# Schematic.net
KiCad netlist of a schematic drawn in Altium Designer
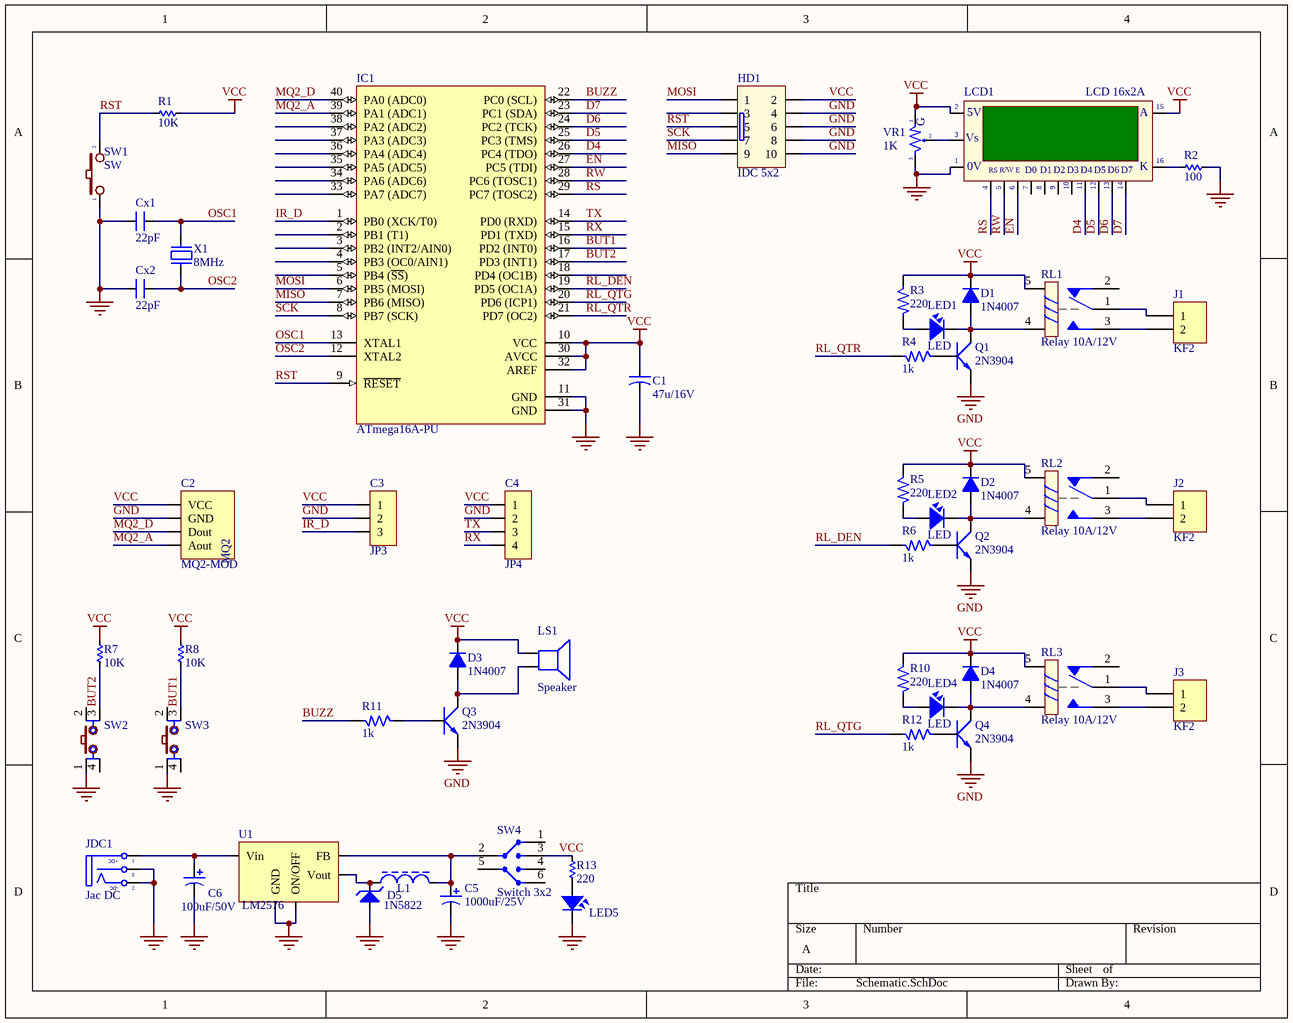
[diagram p0: Schematic.SchDoc]

(export (version "E")
  (design (tool "Eeschema 10.0.6"))
  (components
    (comp (ref "C1")
      (value "47u/16V")
      (footprint "CA-ALU-2.54")
      (description "Capacitor (Semiconductor SIM Model)")
      (fields (field (name "PUBLISHER") "Altium Limited"))
      (libsource (lib "Library") (part "CN-ALU-DIP"))
    )
    (comp (ref "C2")
      (value "MQ2-MOD")
      (footprint "MQ2-MODULE")
      (fields
        (field (name "MANUFACTURER") "Würth Elektronik eiSos GmbH")
        (field (name "PARTNO") "613004143121")
        (field (name "CREATED BY") "Karrer Zheng")
      )
      (libsource (lib "Library") (part "MQ2-MOD"))
    )
    (comp (ref "C3")
      (value "JP3")
      (footprint "JP3-D1T")
      (description "WR-PHD 2.54 mm Angled Socket Header")
      (fields
        (field (name "MANUFACTURER") "Würth Elektronik eiSos GmbH")
        (field (name "PARTNO") "613003143121")
        (field (name "CREATED BY") "Karrer Zheng")
      )
      (libsource (lib "Library") (part "JP3"))
    )
    (comp (ref "C4")
      (value "JP4")
      (footprint "JP4-C1T")
      (description "WR-PHD 2.54 mm Angled Socket Header")
      (fields
        (field (name "MANUFACTURER") "Würth Elektronik eiSos GmbH")
        (field (name "PARTNO") "613004143121")
        (field (name "CREATED BY") "Karrer Zheng")
      )
      (libsource (lib "Library") (part "JP4"))
    )
    (comp (ref "C5")
      (value "1000uF/25V")
      (footprint "CE_12.5x20")
      (description "Cap P  1000uF/16V - 220uF/50V")
      (fields (field (name "Comment") "CP4"))
      (libsource (lib "AS50") (part "CP4"))
    )
    (comp (ref "C6")
      (value "100uF/50V")
      (footprint "CE_8x12")
      (description "Cap P  470uF/16V - 100uF?35V")
      (fields (field (name "Comment") "CP3"))
      (libsource (lib "AS50") (part "CP3"))
    )
    (comp (ref "Cx1") (value "22pF") (footprint "CN1") (libsource (lib "Library") (part "CN")))
    (comp (ref "Cx2") (value "22pF") (footprint "CN1") (libsource (lib "Library") (part "CN")))
    (comp (ref "D1")
      (value "1N4007")
      (footprint "DIO-1A-SMALL")
      (description "Diode 1A")
      (libsource (lib "syhaunguyen") (part "D1A"))
    )
    (comp (ref "D2")
      (value "1N4007")
      (footprint "DIO-1A-SMALL")
      (description "Diode 1A")
      (libsource (lib "syhaunguyen") (part "D1A"))
    )
    (comp (ref "D3")
      (value "1N4007")
      (footprint "DIO-1A-SMALL")
      (description "Diode 1A")
      (libsource (lib "syhaunguyen") (part "D1A"))
    )
    (comp (ref "D4")
      (value "1N4007")
      (footprint "DIO-1A-SMALL")
      (description "Diode 1A")
      (libsource (lib "syhaunguyen") (part "D1A"))
    )
    (comp (ref "D5") (value "1N5822") (footprint "D5A") (libsource (lib "AS50") (part "1N5822")))
    (comp (ref "HD1") (value "IDC 5x2") (footprint "IDC10") (libsource (lib "Library") (part "IDC 5X2")))
    (comp (ref "IC1")
      (value "ATmega16A-PU")
      (footprint "DIP40/W0.6")
      (description "8-Bit AVR Microcontroller with 16K Bytes of In-System Programmable Flash Memory")
      (libsource (lib "Library") (part "ATmega16A-PU"))
    )
    (comp (ref "J1")
      (value "KF2")
      (footprint "KF2-5.08")
      (fields
        (field (name "MANUFACTURER") "Würth Elektronik eiSos GmbH")
        (field (name "PARTNO") "691103110002")
        (field (name "CREATED BY") "Karrer Zheng")
      )
      (libsource (lib "Library") (part "KF2"))
    )
    (comp (ref "J2")
      (value "KF2")
      (footprint "KF2-5.08")
      (fields
        (field (name "MANUFACTURER") "Würth Elektronik eiSos GmbH")
        (field (name "PARTNO") "691103110002")
        (field (name "CREATED BY") "Karrer Zheng")
      )
      (libsource (lib "Library") (part "KF2"))
    )
    (comp (ref "J3")
      (value "KF2")
      (footprint "KF2-5.08")
      (fields
        (field (name "MANUFACTURER") "Würth Elektronik eiSos GmbH")
        (field (name "PARTNO") "691103110002")
        (field (name "CREATED BY") "Karrer Zheng")
      )
      (libsource (lib "Library") (part "KF2"))
    )
    (comp (ref "JDC1")
      (value "Jac DC")
      (footprint "DC0")
      (description "Jac DC input")
      (libsource (lib "Library") (part "DCIN"))
    )
    (comp (ref "L1") (value "INDUCTOR") (footprint "L") (libsource (lib "AS50") (part "INDUCTOR")))
    (comp (ref "LCD1")
      (value "LCD 16x2A")
      (footprint "LCD16X2N")
      (description "LCD dipslay 16 char, 2 line")
      (libsource (lib "Library") (part "LCD16x2A"))
    )
    (comp (ref "LED1")
      (value "LED")
      (footprint "LED-3MM-RED")
      (description "LED Single colour Green and Red")
      (libsource (lib "syhaunguyen") (part "LED"))
    )
    (comp (ref "LED2")
      (value "LED")
      (footprint "LED-3MM-RED")
      (description "LED Single colour Green and Red")
      (libsource (lib "syhaunguyen") (part "LED"))
    )
    (comp (ref "LED4")
      (value "LED")
      (footprint "LED-3MM-RED")
      (description "LED Single colour Green and Red")
      (libsource (lib "syhaunguyen") (part "LED"))
    )
    (comp (ref "LED5") (value "LED") (footprint "LED-3MM-RED") (libsource (lib "Library") (part "LED SMD")))
    (comp (ref "LS1")
      (value "Speaker")
      (footprint "SPEAKER")
      (description "Loudspeaker")
      (fields (field (name "PUBLISHER") "Altium Limited"))
      (libsource (lib "Library") (part "Speaker"))
    )
    (comp (ref "Q1")
      (value "2N3904")
      (footprint "TO92-123")
      (description "NPN 600mW, ECB")
      (libsource (lib "Library") (part "2N904"))
    )
    (comp (ref "Q2")
      (value "2N3904")
      (footprint "TO92-123")
      (description "NPN 600mW, ECB")
      (libsource (lib "Library") (part "2N904"))
    )
    (comp (ref "Q3")
      (value "2N3904")
      (footprint "TO92-123")
      (description "NPN 600mW, ECB")
      (libsource (lib "Library") (part "2N904"))
    )
    (comp (ref "Q4")
      (value "2N3904")
      (footprint "TO92-123")
      (description "NPN 600mW, ECB")
      (libsource (lib "Library") (part "2N904"))
    )
    (comp (ref "R1")
      (value "10K")
      (footprint "RES-1/4W-SMALL")
      (description "Resistor")
      (fields
        (field (name "MANUFACTURER") "Generic Components")
        (field (name "PUBLISHER") "Altium Hobart Technology Centre")
      )
      (libsource (lib "Library") (part "Res-SMD"))
    )
    (comp (ref "R2")
      (value "100")
      (footprint "RES-1/4W-SMALL")
      (description "Resistor")
      (fields
        (field (name "MANUFACTURER") "Generic Components")
        (field (name "PUBLISHER") "Altium Hobart Technology Centre")
      )
      (libsource (lib "Library") (part "Res-SMD"))
    )
    (comp (ref "R3")
      (value "220")
      (footprint "RES-1/4W-SMALL")
      (description "Resistor 1/4W")
      (libsource (lib "syhaunguyen") (part "R"))
    )
    (comp (ref "R4")
      (value "1k")
      (footprint "RES-1/4W-SMALL")
      (description "Resistor 1/4W")
      (libsource (lib "syhaunguyen") (part "R"))
    )
    (comp (ref "R5")
      (value "220")
      (footprint "RES-1/4W-SMALL")
      (description "Resistor 1/4W")
      (libsource (lib "syhaunguyen") (part "R"))
    )
    (comp (ref "R6")
      (value "1k")
      (footprint "RES-1/4W-SMALL")
      (description "Resistor 1/4W")
      (libsource (lib "syhaunguyen") (part "R"))
    )
    (comp (ref "R7")
      (value "10K")
      (footprint "RES-1/4W-SMALL")
      (description "Resistor")
      (fields
        (field (name "MANUFACTURER") "Generic Components")
        (field (name "PUBLISHER") "Altium Hobart Technology Centre")
      )
      (libsource (lib "Library") (part "Res-SMD"))
    )
    (comp (ref "R8")
      (value "10K")
      (footprint "RES-1/4W-SMALL")
      (description "Resistor")
      (fields
        (field (name "MANUFACTURER") "Generic Components")
        (field (name "PUBLISHER") "Altium Hobart Technology Centre")
      )
      (libsource (lib "Library") (part "Res-SMD"))
    )
    (comp (ref "R10")
      (value "220")
      (footprint "RES-1/4W-SMALL")
      (description "Resistor 1/4W")
      (libsource (lib "syhaunguyen") (part "R"))
    )
    (comp (ref "R11")
      (value "1k")
      (footprint "RES-1/4W-SMALL")
      (description "Resistor 1/4W")
      (libsource (lib "syhaunguyen") (part "R"))
    )
    (comp (ref "R12")
      (value "1k")
      (footprint "RES-1/4W-SMALL")
      (description "Resistor 1/4W")
      (libsource (lib "syhaunguyen") (part "R"))
    )
    (comp (ref "R13")
      (value "220")
      (footprint "RES-1/4W-SMALL")
      (description "Resistor")
      (fields
        (field (name "MANUFACTURER") "Generic Components")
        (field (name "PUBLISHER") "Altium Hobart Technology Centre")
      )
      (libsource (lib "Library") (part "Res-SMD"))
    )
    (comp (ref "RL1")
      (value "Relay 10A/12V")
      (footprint "RELAY 5")
      (description "Relay SPDT,10A - 12VDC 5 Pin")
      (libsource (lib "Library") (part "Relay 5"))
    )
    (comp (ref "RL2")
      (value "Relay 10A/12V")
      (footprint "RELAY 5")
      (description "Relay SPDT,10A - 12VDC 5 Pin")
      (libsource (lib "Library") (part "Relay 5"))
    )
    (comp (ref "RL3")
      (value "Relay 10A/12V")
      (footprint "RELAY 5")
      (description "Relay SPDT,10A - 12VDC 5 Pin")
      (libsource (lib "Library") (part "Relay 5"))
    )
    (comp (ref "SW1")
      (value "SW")
      (footprint "SW2_6x6x6.5")
      (description "Switch button 2 pin")
      (libsource (lib "Library") (part "SW2"))
    )
    (comp (ref "SW2")
      (value "SW")
      (footprint "SW4-12x12x8")
      (description "Switch button 4 pin")
      (libsource (lib "Library") (part "SW4"))
    )
    (comp (ref "SW3")
      (value "SW")
      (footprint "SW4-12x12x8")
      (description "Switch button 4 pin")
      (libsource (lib "Library") (part "SW4"))
    )
    (comp (ref "SW4") (value "Switch 3x2") (footprint "SW3-DIP") (libsource (lib "Library") (part "SW3x2")))
    (comp (ref "U1")
      (value "LM2576")
      (footprint "TO-220_5")
      (description "3A Step-down Voltage Regulator")
      (libsource (lib "AS50") (part "LM2576"))
    )
    (comp (ref "VR1")
      (value "1K")
      (footprint "VR-S2")
      (description "Var Resistor")
      (libsource (lib "Library") (part "VR-S"))
    )
    (comp (ref "X1")
      (value "8MHz")
      (footprint "XT2")
      (description "Crystal, 32.768 KHz, -40 to 85 degC, 3.2 x 1.5 x 0.9 mm SMD")
      (libsource (lib "Library") (part "XT2"))
    )
  )
  (nets
    (net (code "1") (name "/BUT1") (class "Default")
      (node (ref "IC1") (pin "16") (pinfunction "PD2_(INT0)_16") (pintype "bidirectional"))
      (node (ref "R8") (pin "1") (pinfunction "1_1") (pintype "passive"))
      (node (ref "SW3") (pin "3") (pinfunction "3_3") (pintype "passive"))
    )
    (net (code "2") (name "/BUT2") (class "Default")
      (node (ref "IC1") (pin "17") (pinfunction "PD3_(INT1)_17") (pintype "bidirectional"))
      (node (ref "R7") (pin "1") (pinfunction "1_1") (pintype "passive"))
      (node (ref "SW2") (pin "3") (pinfunction "3_3") (pintype "passive"))
    )
    (net (code "3") (name "/BUZZ") (class "Default")
      (node (ref "IC1") (pin "22") (pinfunction "PC0_(SCL)_22") (pintype "bidirectional"))
      (node (ref "R11") (pin "2") (pinfunction "2_2") (pintype "passive"))
    )
    (net (code "4") (name "/D4") (class "Default")
      (node (ref "IC1") (pin "26") (pinfunction "PC4_(TDO)_26") (pintype "bidirectional"))
      (node (ref "LCD1") (pin "11") (pinfunction "D4_11") (pintype "passive"))
    )
    (net (code "5") (name "/D5") (class "Default")
      (node (ref "IC1") (pin "25") (pinfunction "PC3_(TMS)_25") (pintype "bidirectional"))
      (node (ref "LCD1") (pin "12") (pinfunction "D5_12") (pintype "passive"))
    )
    (net (code "6") (name "/D6") (class "Default")
      (node (ref "IC1") (pin "24") (pinfunction "PC2_(TCK)_24") (pintype "bidirectional"))
      (node (ref "LCD1") (pin "13") (pinfunction "D6_13") (pintype "passive"))
    )
    (net (code "7") (name "/D7") (class "Default")
      (node (ref "IC1") (pin "23") (pinfunction "PC1_(SDA)_23") (pintype "bidirectional"))
      (node (ref "LCD1") (pin "14") (pinfunction "D7_14") (pintype "passive"))
    )
    (net (code "8") (name "/EN") (class "Default")
      (node (ref "IC1") (pin "27") (pinfunction "PC5_(TDI)_27") (pintype "bidirectional"))
      (node (ref "LCD1") (pin "6") (pinfunction "~{EN}_6") (pintype "passive"))
    )
    (net (code "9") (name "/IR_D") (class "Default")
      (node (ref "C3") (pin "3") (pinfunction "3_3") (pintype "passive"))
      (node (ref "IC1") (pin "1") (pinfunction "PB0_(XCK/T0)_1") (pintype "bidirectional"))
    )
    (net (code "10") (name "/MISO") (class "Default")
      (node (ref "HD1") (pin "9") (pinfunction "9_9") (pintype "passive"))
      (node (ref "IC1") (pin "7") (pinfunction "PB6_(MISO)_7") (pintype "bidirectional"))
    )
    (net (code "11") (name "/MOSI") (class "Default")
      (node (ref "HD1") (pin "1") (pinfunction "1_1") (pintype "passive"))
      (node (ref "IC1") (pin "6") (pinfunction "PB5_(MOSI)_6") (pintype "bidirectional"))
    )
    (net (code "12") (name "/MQ2_A") (class "Default")
      (node (ref "C2") (pin "1") (pinfunction "Aout_1") (pintype "passive"))
      (node (ref "IC1") (pin "39") (pinfunction "PA1_(ADC1)_39") (pintype "bidirectional"))
    )
    (net (code "13") (name "/MQ2_D") (class "Default")
      (node (ref "C2") (pin "2") (pinfunction "Dout_2") (pintype "passive"))
      (node (ref "IC1") (pin "40") (pinfunction "PA0_(ADC0)_40") (pintype "bidirectional"))
    )
    (net (code "14") (name "/OSC1") (class "Default")
      (node (ref "Cx1") (pin "2") (pinfunction "2_2") (pintype "passive"))
      (node (ref "IC1") (pin "13") (pinfunction "XTAL1_13") (pintype "passive"))
      (node (ref "X1") (pin "2") (pinfunction "2_2") (pintype "passive"))
    )
    (net (code "15") (name "/OSC2") (class "Default")
      (node (ref "Cx2") (pin "2") (pinfunction "2_2") (pintype "passive"))
      (node (ref "IC1") (pin "12") (pinfunction "XTAL2_12") (pintype "passive"))
      (node (ref "X1") (pin "1") (pinfunction "1_1") (pintype "passive"))
    )
    (net (code "16") (name "/RL_DEN") (class "Default")
      (node (ref "IC1") (pin "19") (pinfunction "PD5_(OC1A)_19") (pintype "bidirectional"))
      (node (ref "R6") (pin "2") (pinfunction "2_2") (pintype "passive"))
    )
    (net (code "17") (name "/RL_QTG") (class "Default")
      (node (ref "IC1") (pin "20") (pinfunction "PD6_(ICP1)_20") (pintype "bidirectional"))
      (node (ref "R12") (pin "2") (pinfunction "2_2") (pintype "passive"))
    )
    (net (code "18") (name "/RL_QTR") (class "Default")
      (node (ref "IC1") (pin "21") (pinfunction "PD7_(OC2)_21") (pintype "bidirectional"))
      (node (ref "R4") (pin "2") (pinfunction "2_2") (pintype "passive"))
    )
    (net (code "19") (name "/RS") (class "Default")
      (node (ref "IC1") (pin "29") (pinfunction "PC7_(TOSC2)_29") (pintype "bidirectional"))
      (node (ref "LCD1") (pin "4") (pinfunction "RS_4") (pintype "passive"))
    )
    (net (code "20") (name "/RST") (class "Default")
      (node (ref "HD1") (pin "5") (pinfunction "5_5") (pintype "passive"))
      (node (ref "IC1") (pin "9") (pinfunction "~{RESET}_9") (pintype "input"))
      (node (ref "R1") (pin "2") (pinfunction "2_2") (pintype "passive"))
      (node (ref "SW1") (pin "2") (pinfunction "2_2") (pintype "passive"))
    )
    (net (code "21") (name "/RW") (class "Default")
      (node (ref "IC1") (pin "28") (pinfunction "PC6_(TOSC1)_28") (pintype "bidirectional"))
      (node (ref "LCD1") (pin "5") (pinfunction "R/~{W}_5") (pintype "passive"))
    )
    (net (code "22") (name "/RX") (class "Default")
      (node (ref "C4") (pin "4") (pinfunction "4_4") (pintype "passive"))
      (node (ref "IC1") (pin "15") (pinfunction "PD1_(TXD)_15") (pintype "bidirectional"))
    )
    (net (code "23") (name "/SCK") (class "Default")
      (node (ref "HD1") (pin "7") (pinfunction "7_7") (pintype "passive"))
      (node (ref "IC1") (pin "8") (pinfunction "PB7_(SCK)_8") (pintype "bidirectional"))
    )
    (net (code "24") (name "/TX") (class "Default")
      (node (ref "C4") (pin "3") (pinfunction "3_3") (pintype "passive"))
      (node (ref "IC1") (pin "14") (pinfunction "PD0_(RXD)_14") (pintype "bidirectional"))
    )
    (net (code "25") (name "GND") (class "Default")
      (node (ref "C1") (pin "2") (pinfunction "2_2") (pintype "passive"))
      (node (ref "C2") (pin "3") (pinfunction "GND_3") (pintype "passive"))
      (node (ref "C3") (pin "2") (pinfunction "2_2") (pintype "passive"))
      (node (ref "C4") (pin "2") (pinfunction "2_2") (pintype "passive"))
      (node (ref "C5") (pin "2") (pinfunction "2_2") (pintype "passive"))
      (node (ref "C6") (pin "2") (pinfunction "2_2") (pintype "passive"))
      (node (ref "Cx1") (pin "1") (pinfunction "1_1") (pintype "passive"))
      (node (ref "Cx2") (pin "1") (pinfunction "1_1") (pintype "passive"))
      (node (ref "D5") (pin "1") (pinfunction "1_1") (pintype "passive"))
      (node (ref "HD1") (pin "10") (pinfunction "10_10") (pintype "passive"))
      (node (ref "HD1") (pin "4") (pinfunction "4_4") (pintype "passive"))
      (node (ref "HD1") (pin "6") (pinfunction "6_6") (pintype "passive"))
      (node (ref "HD1") (pin "8") (pinfunction "8_8") (pintype "passive"))
      (node (ref "IC1") (pin "11") (pinfunction "GND_11") (pintype "power_in"))
      (node (ref "IC1") (pin "31") (pinfunction "GND_31") (pintype "power_in"))
      (node (ref "JDC1") (pin "2") (pinfunction "TN_2") (pintype "passive"))
      (node (ref "JDC1") (pin "3") (pinfunction "S_3") (pintype "power_in"))
      (node (ref "LCD1") (pin "1") (pinfunction "GND_1") (pintype "passive"))
      (node (ref "LED5") (pin "2") (pinfunction "2_2") (pintype "passive"))
      (node (ref "Q1") (pin "1") (pinfunction "E_1") (pintype "passive"))
      (node (ref "Q2") (pin "1") (pinfunction "E_1") (pintype "passive"))
      (node (ref "Q3") (pin "1") (pinfunction "E_1") (pintype "passive"))
      (node (ref "Q4") (pin "1") (pinfunction "E_1") (pintype "passive"))
      (node (ref "R2") (pin "1") (pinfunction "1_1") (pintype "passive"))
      (node (ref "SW1") (pin "1") (pinfunction "1_1") (pintype "passive"))
      (node (ref "SW2") (pin "1") (pintype "passive"))
      (node (ref "SW3") (pin "1") (pintype "passive"))
      (node (ref "U1") (pin "3") (pinfunction "GND_3") (pintype "passive"))
      (node (ref "U1") (pin "5") (pinfunction "ON/OFF_5") (pintype "passive"))
      (node (ref "VR1") (pin "3") (pinfunction "3_3") (pintype "passive"))
    )
    (net (code "26") (name "Net-(D1-A)") (class "Default")
      (node (ref "D1") (pin "1") (pinfunction "A_1") (pintype "passive"))
      (node (ref "LED1") (pin "2") (pinfunction "2_2") (pintype "passive"))
      (node (ref "Q1") (pin "3") (pinfunction "C_3") (pintype "passive"))
      (node (ref "RL1") (pin "4") (pinfunction "4_4") (pintype "passive"))
    )
    (net (code "27") (name "Net-(D2-A)") (class "Default")
      (node (ref "D2") (pin "1") (pinfunction "A_1") (pintype "passive"))
      (node (ref "LED2") (pin "2") (pinfunction "2_2") (pintype "passive"))
      (node (ref "Q2") (pin "3") (pinfunction "C_3") (pintype "passive"))
      (node (ref "RL2") (pin "4") (pinfunction "4_4") (pintype "passive"))
    )
    (net (code "28") (name "Net-(D3-A)") (class "Default")
      (node (ref "D3") (pin "1") (pinfunction "A_1") (pintype "passive"))
      (node (ref "LS1") (pin "2") (pinfunction "2_2") (pintype "passive"))
      (node (ref "Q3") (pin "3") (pinfunction "C_3") (pintype "passive"))
    )
    (net (code "29") (name "Net-(D4-A)") (class "Default")
      (node (ref "D4") (pin "1") (pinfunction "A_1") (pintype "passive"))
      (node (ref "LED4") (pin "2") (pinfunction "2_2") (pintype "passive"))
      (node (ref "Q4") (pin "3") (pinfunction "C_3") (pintype "passive"))
      (node (ref "RL3") (pin "4") (pinfunction "4_4") (pintype "passive"))
    )
    (net (code "30") (name "Net-(J1-Pad1)") (class "Default")
      (node (ref "J1") (pin "1") (pinfunction "1_1") (pintype "passive"))
      (node (ref "RL1") (pin "1") (pinfunction "1_1") (pintype "passive"))
    )
    (net (code "31") (name "Net-(J1-Pad2)") (class "Default")
      (node (ref "J1") (pin "2") (pinfunction "2_2") (pintype "passive"))
      (node (ref "RL1") (pin "3") (pinfunction "3_3") (pintype "passive"))
    )
    (net (code "32") (name "Net-(J2-Pad1)") (class "Default")
      (node (ref "J2") (pin "1") (pinfunction "1_1") (pintype "passive"))
      (node (ref "RL2") (pin "1") (pinfunction "1_1") (pintype "passive"))
    )
    (net (code "33") (name "Net-(J2-Pad2)") (class "Default")
      (node (ref "J2") (pin "2") (pinfunction "2_2") (pintype "passive"))
      (node (ref "RL2") (pin "3") (pinfunction "3_3") (pintype "passive"))
    )
    (net (code "34") (name "Net-(J3-Pad1)") (class "Default")
      (node (ref "J3") (pin "1") (pinfunction "1_1") (pintype "passive"))
      (node (ref "RL3") (pin "1") (pinfunction "1_1") (pintype "passive"))
    )
    (net (code "35") (name "Net-(J3-Pad2)") (class "Default")
      (node (ref "J3") (pin "2") (pinfunction "2_2") (pintype "passive"))
      (node (ref "RL3") (pin "3") (pinfunction "3_3") (pintype "passive"))
    )
    (net (code "36") (name "Net-(JDC1-T)") (class "Default")
      (node (ref "C6") (pin "1") (pinfunction "1_1") (pintype "passive"))
      (node (ref "JDC1") (pin "1") (pinfunction "T_1") (pintype "passive"))
      (node (ref "U1") (pin "1") (pinfunction "Vin_1") (pintype "passive"))
    )
    (net (code "37") (name "Net-(LCD1-K)") (class "Default")
      (node (ref "LCD1") (pin "16") (pinfunction "K_16") (pintype "passive"))
      (node (ref "R2") (pin "2") (pinfunction "2_2") (pintype "passive"))
    )
    (net (code "38") (name "Net-(LCD1-VEE)") (class "Default")
      (node (ref "LCD1") (pin "3") (pinfunction "VEE_3") (pintype "passive"))
      (node (ref "VR1") (pin "2") (pinfunction "2_2") (pintype "passive"))
    )
    (net (code "39") (name "Net-(LED1-Pad1)") (class "Default")
      (node (ref "LED1") (pin "1") (pinfunction "1_1") (pintype "passive"))
      (node (ref "R3") (pin "2") (pinfunction "2_2") (pintype "passive"))
    )
    (net (code "40") (name "Net-(LED2-Pad1)") (class "Default")
      (node (ref "LED2") (pin "1") (pinfunction "1_1") (pintype "passive"))
      (node (ref "R5") (pin "2") (pinfunction "2_2") (pintype "passive"))
    )
    (net (code "41") (name "Net-(LED4-Pad1)") (class "Default")
      (node (ref "LED4") (pin "1") (pinfunction "1_1") (pintype "passive"))
      (node (ref "R10") (pin "2") (pinfunction "2_2") (pintype "passive"))
    )
    (net (code "42") (name "Net-(LED5-Pad1)") (class "Default")
      (node (ref "LED5") (pin "1") (pinfunction "1_1") (pintype "passive"))
      (node (ref "R13") (pin "2") (pinfunction "2_2") (pintype "passive"))
    )
    (net (code "43") (name "Net-(Q1-B)") (class "Default")
      (node (ref "Q1") (pin "2") (pinfunction "B_2") (pintype "passive"))
      (node (ref "R4") (pin "1") (pinfunction "1_1") (pintype "passive"))
    )
    (net (code "44") (name "Net-(Q2-B)") (class "Default")
      (node (ref "Q2") (pin "2") (pinfunction "B_2") (pintype "passive"))
      (node (ref "R6") (pin "1") (pinfunction "1_1") (pintype "passive"))
    )
    (net (code "45") (name "Net-(Q3-B)") (class "Default")
      (node (ref "Q3") (pin "2") (pinfunction "B_2") (pintype "passive"))
      (node (ref "R11") (pin "1") (pinfunction "1_1") (pintype "passive"))
    )
    (net (code "46") (name "Net-(Q4-B)") (class "Default")
      (node (ref "Q4") (pin "2") (pinfunction "B_2") (pintype "passive"))
      (node (ref "R12") (pin "1") (pinfunction "1_1") (pintype "passive"))
    )
    (net (code "47") (name "Net-(U1-FB)") (class "Default")
      (node (ref "C5") (pin "1") (pinfunction "1_1") (pintype "passive"))
      (node (ref "L1") (pin "2") (pinfunction "2_2") (pintype "passive"))
      (node (ref "SW4") (pin "2") (pintype "passive"))
      (node (ref "U1") (pin "4") (pinfunction "FB_4") (pintype "passive"))
    )
    (net (code "48") (name "Net-(U1-Vout)") (class "Default")
      (node (ref "D5") (pin "2") (pinfunction "2_2") (pintype "passive"))
      (node (ref "L1") (pin "1") (pinfunction "1_1") (pintype "passive"))
      (node (ref "U1") (pin "2") (pinfunction "Vout_2") (pintype "passive"))
    )
    (net (code "49") (name "VCC") (class "Default")
      (node (ref "C1") (pin "1") (pinfunction "1_1") (pintype "passive"))
      (node (ref "C2") (pin "4") (pinfunction "VCC_4") (pintype "passive"))
      (node (ref "C3") (pin "1") (pinfunction "1_1") (pintype "passive"))
      (node (ref "C4") (pin "1") (pinfunction "1_1") (pintype "passive"))
      (node (ref "D1") (pin "2") (pinfunction "K_2") (pintype "passive"))
      (node (ref "D2") (pin "2") (pinfunction "K_2") (pintype "passive"))
      (node (ref "D3") (pin "2") (pinfunction "K_2") (pintype "passive"))
      (node (ref "D4") (pin "2") (pinfunction "K_2") (pintype "passive"))
      (node (ref "HD1") (pin "2") (pinfunction "2_2") (pintype "passive"))
      (node (ref "IC1") (pin "10") (pinfunction "VCC_10") (pintype "power_in"))
      (node (ref "IC1") (pin "30") (pinfunction "AVCC_30") (pintype "power_in"))
      (node (ref "IC1") (pin "32") (pinfunction "AREF_32") (pintype "power_in"))
      (node (ref "LCD1") (pin "15") (pinfunction "A_15") (pintype "passive"))
      (node (ref "LCD1") (pin "2") (pinfunction "VDD_2") (pintype "passive"))
      (node (ref "LS1") (pin "1") (pinfunction "1_1") (pintype "passive"))
      (node (ref "R1") (pin "1") (pinfunction "1_1") (pintype "passive"))
      (node (ref "R10") (pin "1") (pinfunction "1_1") (pintype "passive"))
      (node (ref "R13") (pin "1") (pinfunction "1_1") (pintype "passive"))
      (node (ref "R3") (pin "1") (pinfunction "1_1") (pintype "passive"))
      (node (ref "R5") (pin "1") (pinfunction "1_1") (pintype "passive"))
      (node (ref "R7") (pin "2") (pinfunction "2_2") (pintype "passive"))
      (node (ref "R8") (pin "2") (pinfunction "2_2") (pintype "passive"))
      (node (ref "RL1") (pin "5") (pinfunction "5_5") (pintype "passive"))
      (node (ref "RL2") (pin "5") (pinfunction "5_5") (pintype "passive"))
      (node (ref "RL3") (pin "5") (pinfunction "5_5") (pintype "passive"))
      (node (ref "SW4") (pin "3") (pinfunction "I/O2_3") (pintype "passive"))
      (node (ref "VR1") (pin "1") (pinfunction "1_1") (pintype "passive"))
    )
    (net (code "50") (name "unconnected-(HD1-Pad3)") (class "Default")
      (node (ref "HD1") (pin "3") (pinfunction "3_3") (pintype "passive"))
    )
    (net (code "51") (name "unconnected-(IC1-PA2_(ADC2)-Pad38)") (class "Default")
      (node (ref "IC1") (pin "38") (pinfunction "PA2_(ADC2)_38") (pintype "bidirectional"))
    )
    (net (code "52") (name "unconnected-(IC1-PA3_(ADC3)-Pad37)") (class "Default")
      (node (ref "IC1") (pin "37") (pinfunction "PA3_(ADC3)_37") (pintype "bidirectional"))
    )
    (net (code "53") (name "unconnected-(IC1-PA4_(ADC4)-Pad36)") (class "Default")
      (node (ref "IC1") (pin "36") (pinfunction "PA4_(ADC4)_36") (pintype "bidirectional"))
    )
    (net (code "54") (name "unconnected-(IC1-PA5_(ADC5)-Pad35)") (class "Default")
      (node (ref "IC1") (pin "35") (pinfunction "PA5_(ADC5)_35") (pintype "bidirectional"))
    )
    (net (code "55") (name "unconnected-(IC1-PA6_(ADC6)-Pad34)") (class "Default")
      (node (ref "IC1") (pin "34") (pinfunction "PA6_(ADC6)_34") (pintype "bidirectional"))
    )
    (net (code "56") (name "unconnected-(IC1-PA7_(ADC7)-Pad33)") (class "Default")
      (node (ref "IC1") (pin "33") (pinfunction "PA7_(ADC7)_33") (pintype "bidirectional"))
    )
    (net (code "57") (name "unconnected-(IC1-PB1_(T1)-Pad2)") (class "Default")
      (node (ref "IC1") (pin "2") (pinfunction "PB1_(T1)_2") (pintype "bidirectional"))
    )
    (net (code "58") (name "unconnected-(IC1-PB2_(INT2{slash}AIN0)-Pad3)") (class "Default")
      (node (ref "IC1") (pin "3") (pinfunction "PB2_(INT2/AIN0)_3") (pintype "bidirectional"))
    )
    (net (code "59") (name "unconnected-(IC1-PB3_(OC0{slash}AIN1)-Pad4)") (class "Default")
      (node (ref "IC1") (pin "4") (pinfunction "PB3_(OC0/AIN1)_4") (pintype "bidirectional"))
    )
    (net (code "60") (name "unconnected-(IC1-PB4_(~{SS})-Pad5)") (class "Default")
      (node (ref "IC1") (pin "5") (pinfunction "PB4_(~{SS})_5") (pintype "bidirectional"))
    )
    (net (code "61") (name "unconnected-(IC1-PD4_(OC1B)-Pad18)") (class "Default")
      (node (ref "IC1") (pin "18") (pinfunction "PD4_(OC1B)_18") (pintype "bidirectional"))
    )
    (net (code "62") (name "unconnected-(LCD1-D0-Pad7)") (class "Default")
      (node (ref "LCD1") (pin "7") (pinfunction "D0_7") (pintype "passive"))
    )
    (net (code "63") (name "unconnected-(LCD1-D1-Pad8)") (class "Default")
      (node (ref "LCD1") (pin "8") (pinfunction "D1_8") (pintype "passive"))
    )
    (net (code "64") (name "unconnected-(LCD1-D2-Pad9)") (class "Default")
      (node (ref "LCD1") (pin "9") (pinfunction "D2_9") (pintype "passive"))
    )
    (net (code "65") (name "unconnected-(LCD1-D3-Pad10)") (class "Default")
      (node (ref "LCD1") (pin "10") (pinfunction "D3_10") (pintype "passive"))
    )
    (net (code "66") (name "unconnected-(RL1-Pad2)") (class "Default")
      (node (ref "RL1") (pin "2") (pinfunction "2_2") (pintype "passive"))
    )
    (net (code "67") (name "unconnected-(RL2-Pad2)") (class "Default")
      (node (ref "RL2") (pin "2") (pinfunction "2_2") (pintype "passive"))
    )
    (net (code "68") (name "unconnected-(RL3-Pad2)") (class "Default")
      (node (ref "RL3") (pin "2") (pinfunction "2_2") (pintype "passive"))
    )
    (net (code "69") (name "unconnected-(SW2-Pad2)") (class "Default")
      (node (ref "SW2") (pin "2") (pinfunction "2_2") (pintype "passive"))
    )
    (net (code "70") (name "unconnected-(SW2-Pad4)") (class "Default")
      (node (ref "SW2") (pin "4") (pinfunction "4_4") (pintype "passive"))
    )
    (net (code "71") (name "unconnected-(SW3-Pad2)") (class "Default")
      (node (ref "SW3") (pin "2") (pinfunction "2_2") (pintype "passive"))
    )
    (net (code "72") (name "unconnected-(SW3-Pad4)") (class "Default")
      (node (ref "SW3") (pin "4") (pinfunction "4_4") (pintype "passive"))
    )
    (net (code "73") (name "unconnected-(SW4-6-Pad5)") (class "Default")
      (node (ref "SW4") (pin "5") (pinfunction "6_5") (pintype "passive"))
    )
    (net (code "74") (name "unconnected-(SW4-Pad1)") (class "Default")
      (node (ref "SW4") (pin "1") (pintype "passive"))
    )
    (net (code "75") (name "unconnected-(SW4-Pad4)") (class "Default")
      (node (ref "SW4") (pin "4") (pintype "passive"))
    )
    (net (code "76") (name "unconnected-(SW4-Pad6)") (class "Default")
      (node (ref "SW4") (pin "6") (pintype "passive"))
    )
  )
)
